# motor.net
KiCad netlist of a schematic drawn in Altium Designer
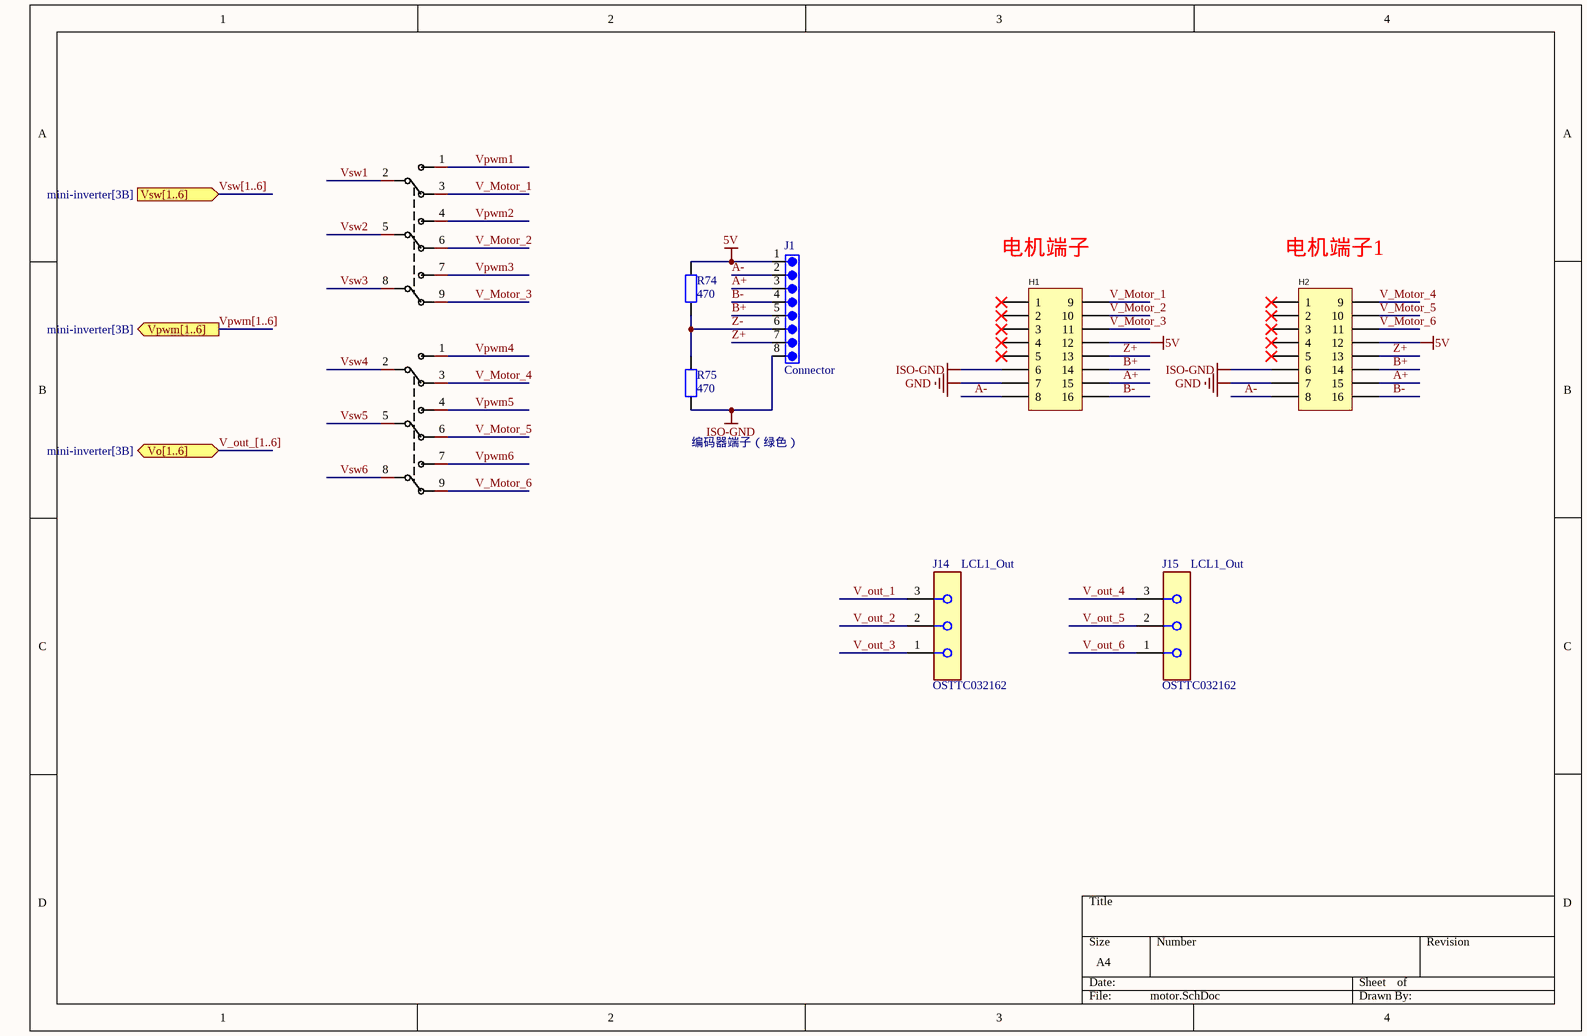
[diagram p0: motor.SchDoc]

(export (version "E")
  (design (tool "Eeschema 10.0.6"))
  (components
    (comp (ref "H1")
      (value "HC-5557-2*8AW")
      (footprint "CONN-TH_16P-P4.20_5557-2X8AW")
      (fields (field (name "MANUFACTURER") "HCTL(华灿天禄)"))
      (libsource (lib "HC-5557-2_8AW1_HC-5557-2_8AW.schdoc") (part "HC-5557-2*8AW"))
    )
    (comp (ref "H2")
      (value "HC-5557-2*8AW")
      (footprint "CONN-TH_16P-P4.20_5557-2X8AW")
      (fields (field (name "MANUFACTURER") "HCTL(华灿天禄)"))
      (libsource (lib "HC-5557-2_8AW1_HC-5557-2_8AW.schdoc") (part "HC-5557-2*8AW"))
    )
    (comp (ref "J1")
      (value "Connector")
      (footprint "691382010008:691382010008")
      (fields
        (field (name "MANUFACTURER PART NUMBER") "691382010008")
        (field (name "MANUFACTURER") "Wurth Elektronik")
      )
      (libsource (lib "691382010008") (part "691382010008"))
    )
    (comp (ref "J14")
      (value "LCL1_Out")
      (footprint "3 Pin Terminal")
      (description "3 Position Terminal Block 5.08mm")
      (fields
        (field (name "VOLTAGE") "300V")
        (field (name "MANUFACTURER") "On Shore Technology")
        (field (name "PART NUMBER") "OSTTC032162")
      )
      (libsource (lib "FYP_Components") (part "3PinTerminal"))
    )
    (comp (ref "J15")
      (value "LCL1_Out")
      (footprint "3 Pin Terminal")
      (description "3 Position Terminal Block 5.08mm")
      (fields
        (field (name "VOLTAGE") "300V")
        (field (name "MANUFACTURER") "On Shore Technology")
        (field (name "PART NUMBER") "OSTTC032162")
      )
      (libsource (lib "FYP_Components") (part "3PinTerminal"))
    )
    (comp (ref "R74")
      (value "470")
      (footprint "RESC1608X05N")
      (description "贴片电阻")
      (libsource (lib "Simscale") (part "0603 100KΩ (1003) 1%_4"))
    )
    (comp (ref "R75")
      (value "470")
      (footprint "RESC1608X05N")
      (description "贴片电阻")
      (libsource (lib "Simscale") (part "0603 100KΩ (1003) 1%_4"))
    )
    (comp (ref "U18")
      (value "7307TCWZQE")
      (footprint "SW-TH_9P-L12.7-W16.5-P4.7-LS9.6")
      (fields (field (name "MANUFACTURER") "C&K"))
      (libsource (lib "mini-inverter_1") (part "7307TCWZQE"))
    )
    (comp (ref "U19")
      (value "7307TCWZQE")
      (footprint "SW-TH_9P-L12.7-W16.5-P4.7-LS9.6")
      (fields (field (name "MANUFACTURER") "C&K"))
      (libsource (lib "mini-inverter_1") (part "7307TCWZQE"))
    )
  )
  (nets
    (net (code "1") (name "/A+") (class "Default")
      (node (ref "H1") (pin "14") (pinfunction "15_14") (pintype "passive"))
      (node (ref "H2") (pin "14") (pinfunction "15_14") (pintype "passive"))
      (node (ref "J1") (pin "3") (pinfunction "3_3") (pintype "passive"))
    )
    (net (code "2") (name "/A-") (class "Default")
      (node (ref "H1") (pin "15") (pinfunction "8_15") (pintype "passive"))
      (node (ref "H2") (pin "15") (pinfunction "8_15") (pintype "passive"))
      (node (ref "J1") (pin "2") (pinfunction "2_2") (pintype "passive"))
    )
    (net (code "3") (name "/B+") (class "Default")
      (node (ref "H1") (pin "12") (pinfunction "14_12") (pintype "passive"))
      (node (ref "H2") (pin "12") (pinfunction "14_12") (pintype "passive"))
      (node (ref "J1") (pin "5") (pinfunction "5_5") (pintype "passive"))
    )
    (net (code "4") (name "/B-") (class "Default")
      (node (ref "H1") (pin "16") (pinfunction "16_16") (pintype "passive"))
      (node (ref "H2") (pin "16") (pinfunction "16_16") (pintype "passive"))
      (node (ref "J1") (pin "4") (pinfunction "4_4") (pintype "passive"))
    )
    (net (code "5") (name "/V_Motor_1") (class "Default")
      (node (ref "H1") (pin "2") (pinfunction "9_2") (pintype "passive"))
      (node (ref "U18") (pin "3") (pinfunction "3_3") (pintype "passive"))
    )
    (net (code "6") (name "/V_Motor_2") (class "Default")
      (node (ref "H1") (pin "4") (pinfunction "10_4") (pintype "passive"))
      (node (ref "U18") (pin "6") (pinfunction "6_6") (pintype "passive"))
    )
    (net (code "7") (name "/V_Motor_3") (class "Default")
      (node (ref "H1") (pin "6") (pinfunction "11_6") (pintype "passive"))
      (node (ref "U18") (pin "9") (pinfunction "9_9") (pintype "passive"))
    )
    (net (code "8") (name "/V_Motor_4") (class "Default")
      (node (ref "H2") (pin "2") (pinfunction "9_2") (pintype "passive"))
      (node (ref "U19") (pin "3") (pinfunction "3_3") (pintype "passive"))
    )
    (net (code "9") (name "/V_Motor_5") (class "Default")
      (node (ref "H2") (pin "4") (pinfunction "10_4") (pintype "passive"))
      (node (ref "U19") (pin "6") (pinfunction "6_6") (pintype "passive"))
    )
    (net (code "10") (name "/V_Motor_6") (class "Default")
      (node (ref "H2") (pin "6") (pinfunction "11_6") (pintype "passive"))
      (node (ref "U19") (pin "9") (pinfunction "9_9") (pintype "passive"))
    )
    (net (code "11") (name "/V_out_1") (class "Default")
      (node (ref "J14") (pin "3") (pinfunction "3_3") (pintype "passive"))
    )
    (net (code "12") (name "/V_out_2") (class "Default")
      (node (ref "J14") (pin "2") (pinfunction "2_2") (pintype "passive"))
    )
    (net (code "13") (name "/V_out_3") (class "Default")
      (node (ref "J14") (pin "1") (pinfunction "1_1") (pintype "passive"))
    )
    (net (code "14") (name "/V_out_4") (class "Default")
      (node (ref "J15") (pin "3") (pinfunction "3_3") (pintype "passive"))
    )
    (net (code "15") (name "/V_out_5") (class "Default")
      (node (ref "J15") (pin "2") (pinfunction "2_2") (pintype "passive"))
    )
    (net (code "16") (name "/V_out_6") (class "Default")
      (node (ref "J15") (pin "1") (pinfunction "1_1") (pintype "passive"))
    )
    (net (code "18") (name "/Vpwm1") (class "Default")
      (node (ref "U18") (pin "1") (pinfunction "1_1") (pintype "passive"))
    )
    (net (code "19") (name "/Vpwm2") (class "Default")
      (node (ref "U18") (pin "4") (pinfunction "4_4") (pintype "passive"))
    )
    (net (code "20") (name "/Vpwm3") (class "Default")
      (node (ref "U18") (pin "7") (pinfunction "7_7") (pintype "passive"))
    )
    (net (code "21") (name "/Vpwm4") (class "Default")
      (node (ref "U19") (pin "1") (pinfunction "1_1") (pintype "passive"))
    )
    (net (code "22") (name "/Vpwm5") (class "Default")
      (node (ref "U19") (pin "4") (pinfunction "4_4") (pintype "passive"))
    )
    (net (code "23") (name "/Vpwm6") (class "Default")
      (node (ref "U19") (pin "7") (pinfunction "7_7") (pintype "passive"))
    )
    (net (code "25") (name "/Vsw1") (class "Default")
      (node (ref "U18") (pin "2") (pinfunction "2_2") (pintype "passive"))
    )
    (net (code "26") (name "/Vsw2") (class "Default")
      (node (ref "U18") (pin "5") (pinfunction "5_5") (pintype "passive"))
    )
    (net (code "27") (name "/Vsw3") (class "Default")
      (node (ref "U18") (pin "8") (pinfunction "8_8") (pintype "passive"))
    )
    (net (code "28") (name "/Vsw4") (class "Default")
      (node (ref "U19") (pin "2") (pinfunction "2_2") (pintype "passive"))
    )
    (net (code "29") (name "/Vsw5") (class "Default")
      (node (ref "U19") (pin "5") (pinfunction "5_5") (pintype "passive"))
    )
    (net (code "30") (name "/Vsw6") (class "Default")
      (node (ref "U19") (pin "8") (pinfunction "8_8") (pintype "passive"))
    )
    (net (code "32") (name "/Z+") (class "Default")
      (node (ref "H1") (pin "10") (pinfunction "13_10") (pintype "passive"))
      (node (ref "H2") (pin "10") (pinfunction "13_10") (pintype "passive"))
      (node (ref "J1") (pin "7") (pinfunction "7_7") (pintype "passive"))
    )
    (net (code "33") (name "/Z-") (class "Default")
      (node (ref "J1") (pin "6") (pinfunction "6_6") (pintype "passive"))
      (node (ref "R74") (pin "1") (pinfunction "1_1") (pintype "passive"))
      (node (ref "R75") (pin "2") (pinfunction "2_2") (pintype "passive"))
    )
    (net (code "34") (name "5V") (class "Default")
      (node (ref "H1") (pin "8") (pinfunction "12_8") (pintype "passive"))
      (node (ref "H2") (pin "8") (pinfunction "12_8") (pintype "passive"))
      (node (ref "J1") (pin "1") (pinfunction "1_1") (pintype "passive"))
      (node (ref "R74") (pin "2") (pinfunction "2_2") (pintype "passive"))
    )
    (net (code "35") (name "GND") (class "Default")
      (node (ref "H1") (pin "13") (pinfunction "7_13") (pintype "passive"))
      (node (ref "H2") (pin "13") (pinfunction "7_13") (pintype "passive"))
    )
    (net (code "36") (name "ISO-GND") (class "Default")
      (node (ref "H1") (pin "11") (pinfunction "6_11") (pintype "passive"))
      (node (ref "H2") (pin "11") (pinfunction "6_11") (pintype "passive"))
      (node (ref "J1") (pin "8") (pinfunction "8_8") (pintype "passive"))
      (node (ref "R75") (pin "1") (pinfunction "1_1") (pintype "passive"))
    )
    (net (code "37") (name "unconnected-(H1-2-Pad3)") (class "Default")
      (node (ref "H1") (pin "3") (pinfunction "2_3") (pintype "passive+no_connect"))
    )
    (net (code "38") (name "unconnected-(H1-3-Pad5)") (class "Default")
      (node (ref "H1") (pin "5") (pinfunction "3_5") (pintype "passive+no_connect"))
    )
    (net (code "39") (name "unconnected-(H1-4-Pad7)") (class "Default")
      (node (ref "H1") (pin "7") (pinfunction "4_7") (pintype "passive+no_connect"))
    )
    (net (code "40") (name "unconnected-(H1-5-Pad9)") (class "Default")
      (node (ref "H1") (pin "9") (pinfunction "5_9") (pintype "passive+no_connect"))
    )
    (net (code "41") (name "unconnected-(H1-Pad1)") (class "Default")
      (node (ref "H1") (pin "1") (pinfunction "1_1") (pintype "passive+no_connect"))
    )
    (net (code "42") (name "unconnected-(H2-2-Pad3)") (class "Default")
      (node (ref "H2") (pin "3") (pinfunction "2_3") (pintype "passive+no_connect"))
    )
    (net (code "43") (name "unconnected-(H2-3-Pad5)") (class "Default")
      (node (ref "H2") (pin "5") (pinfunction "3_5") (pintype "passive+no_connect"))
    )
    (net (code "44") (name "unconnected-(H2-4-Pad7)") (class "Default")
      (node (ref "H2") (pin "7") (pinfunction "4_7") (pintype "passive+no_connect"))
    )
    (net (code "45") (name "unconnected-(H2-5-Pad9)") (class "Default")
      (node (ref "H2") (pin "9") (pinfunction "5_9") (pintype "passive+no_connect"))
    )
    (net (code "46") (name "unconnected-(H2-Pad1)") (class "Default")
      (node (ref "H2") (pin "1") (pinfunction "1_1") (pintype "passive+no_connect"))
    )
  )
)
